# eprom-programmer3.net
KiCad netlist of a schematic drawn in EAGLE
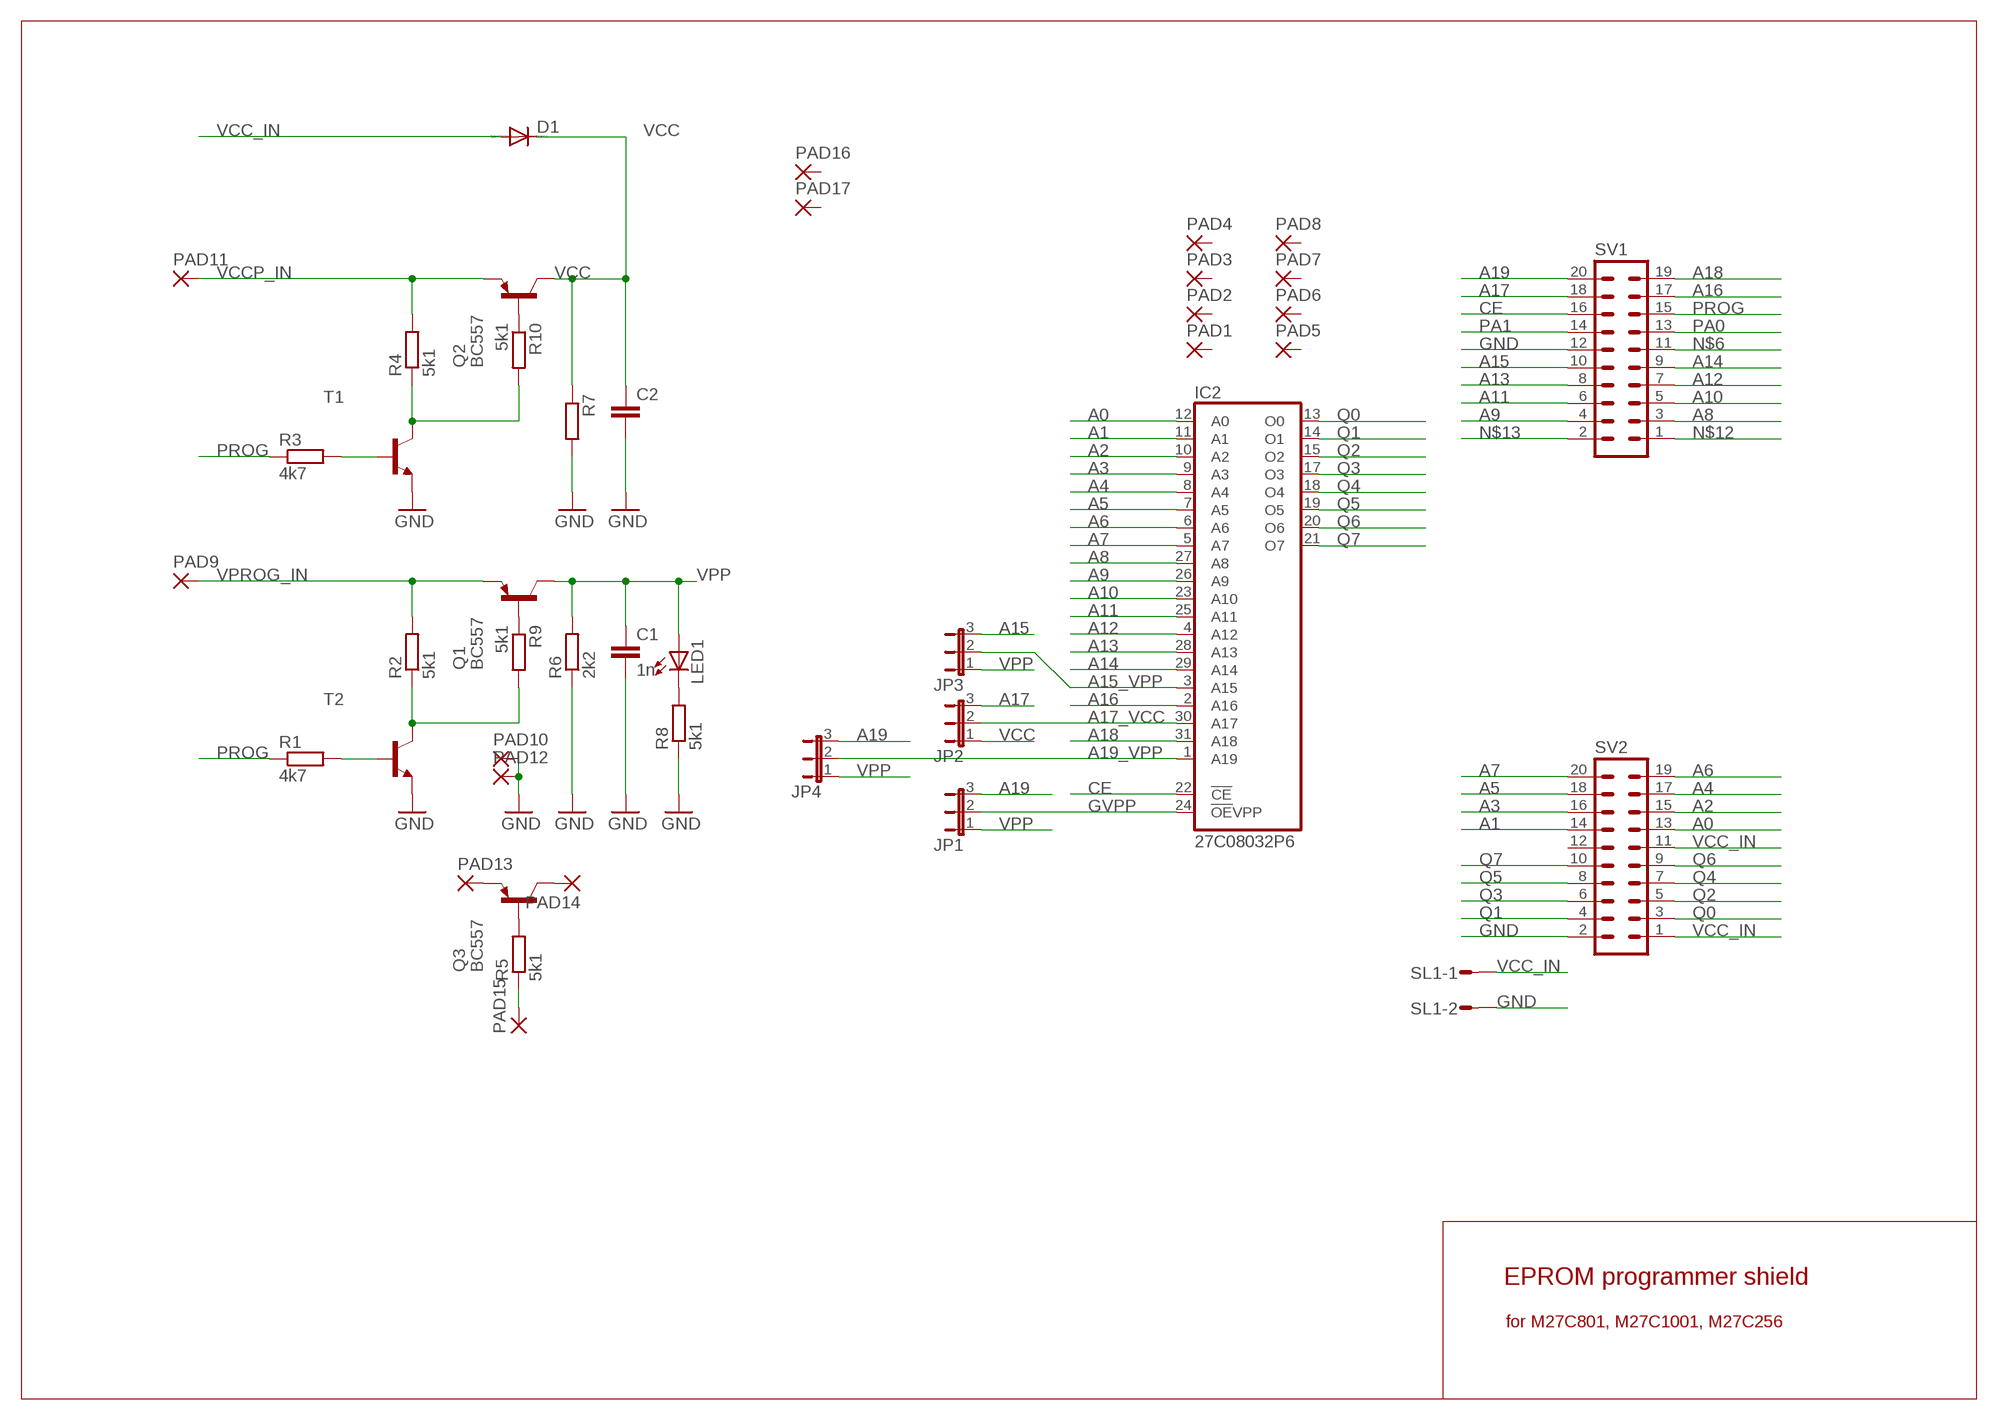
[diagram p0: schematic, sheet 1]

(export (version "E")
  (design (tool "Eeschema 10.0.6"))
  (components
    (comp (ref "C1")
      (value "1n")
      (footprint "eagle-import:C025-024X044")
      (libsource (lib "eagle-import") (part "C-EU025-024X044"))
    )
    (comp (ref "C2")
      (value "C-EUC0805")
      (footprint "eagle-import:C0805")
      (libsource (lib "eagle-import") (part "C-EUC0805"))
    )
    (comp (ref "D1")
      (value "DIODE-MINIMELF")
      (footprint "eagle-import:MINIMELF")
      (libsource (lib "eagle-import") (part "DIODE-MINIMELF"))
    )
    (comp (ref "IC2")
      (value "27C08032P6")
      (footprint "eagle-import:DIL32")
      (fields (field (name "MPN") "AT27C080-90PU"))
      (libsource (lib "eagle-import") (part "27C08032P6"))
    )
    (comp (ref "JP1")
      (value "JP2E")
      (footprint "eagle-import:JP2")
      (libsource (lib "eagle-import") (part "JP2E"))
    )
    (comp (ref "JP2")
      (value "JP2E")
      (footprint "eagle-import:JP2")
      (libsource (lib "eagle-import") (part "JP2E"))
    )
    (comp (ref "JP3")
      (value "JP2E")
      (footprint "eagle-import:JP2")
      (libsource (lib "eagle-import") (part "JP2E"))
    )
    (comp (ref "JP4")
      (value "JP2E")
      (footprint "eagle-import:JP2")
      (libsource (lib "eagle-import") (part "JP2E"))
    )
    (comp (ref "LED1")
      (value "LED3MM")
      (footprint "eagle-import:LED3MM")
      (libsource (lib "eagle-import") (part "LED3MM"))
    )
    (comp (ref "PAD1")
      (value "1,6/0,8")
      (footprint "eagle-import:1,6_0,8")
      (libsource (lib "eagle-import") (part "1,6/0,8"))
    )
    (comp (ref "PAD2")
      (value "1,6/0,8")
      (footprint "eagle-import:1,6_0,8")
      (libsource (lib "eagle-import") (part "1,6/0,8"))
    )
    (comp (ref "PAD3")
      (value "1,6/0,8")
      (footprint "eagle-import:1,6_0,8")
      (libsource (lib "eagle-import") (part "1,6/0,8"))
    )
    (comp (ref "PAD4")
      (value "1,6/0,8")
      (footprint "eagle-import:1,6_0,8")
      (libsource (lib "eagle-import") (part "1,6/0,8"))
    )
    (comp (ref "PAD5")
      (value "1,6/0,8")
      (footprint "eagle-import:1,6_0,8")
      (libsource (lib "eagle-import") (part "1,6/0,8"))
    )
    (comp (ref "PAD6")
      (value "1,6/0,8")
      (footprint "eagle-import:1,6_0,8")
      (libsource (lib "eagle-import") (part "1,6/0,8"))
    )
    (comp (ref "PAD7")
      (value "1,6/0,8")
      (footprint "eagle-import:1,6_0,8")
      (libsource (lib "eagle-import") (part "1,6/0,8"))
    )
    (comp (ref "PAD8")
      (value "1,6/0,8")
      (footprint "eagle-import:1,6_0,8")
      (libsource (lib "eagle-import") (part "1,6/0,8"))
    )
    (comp (ref "PAD9")
      (value "1,6/0,8")
      (footprint "eagle-import:1,6_0,8")
      (libsource (lib "eagle-import") (part "1,6/0,8"))
    )
    (comp (ref "PAD10")
      (value "1,6/0,8")
      (footprint "eagle-import:1,6_0,8")
      (libsource (lib "eagle-import") (part "1,6/0,8"))
    )
    (comp (ref "PAD11")
      (value "1,6/0,8")
      (footprint "eagle-import:1,6_0,8")
      (libsource (lib "eagle-import") (part "1,6/0,8"))
    )
    (comp (ref "PAD12")
      (value "1,6/0,8")
      (footprint "eagle-import:1,6_0,8")
      (libsource (lib "eagle-import") (part "1,6/0,8"))
    )
    (comp (ref "PAD13")
      (value "1,6/0,8")
      (footprint "eagle-import:1,6_0,8")
      (libsource (lib "eagle-import") (part "1,6/0,8"))
    )
    (comp (ref "PAD14")
      (value "1,6/0,8")
      (footprint "eagle-import:1,6_0,8")
      (libsource (lib "eagle-import") (part "1,6/0,8"))
    )
    (comp (ref "PAD15")
      (value "1,6/0,8")
      (footprint "eagle-import:1,6_0,8")
      (libsource (lib "eagle-import") (part "1,6/0,8"))
    )
    (comp (ref "PAD16")
      (value "1,6/0,8")
      (footprint "eagle-import:1,6_0,8")
      (libsource (lib "eagle-import") (part "1,6/0,8"))
    )
    (comp (ref "PAD17")
      (value "1,6/0,8")
      (footprint "eagle-import:1,6_0,8")
      (libsource (lib "eagle-import") (part "1,6/0,8"))
    )
    (comp (ref "Q1")
      (value "BC557")
      (footprint "eagle-import:TO92-EBC")
      (libsource (lib "eagle-import") (part "BC557"))
    )
    (comp (ref "Q2")
      (value "BC557")
      (footprint "eagle-import:TO92-EBC")
      (libsource (lib "eagle-import") (part "BC557"))
    )
    (comp (ref "Q3")
      (value "BC557")
      (footprint "eagle-import:TO92-EBC")
      (libsource (lib "eagle-import") (part "BC557"))
    )
    (comp (ref "R1")
      (value "4k7")
      (footprint "eagle-import:0207_2V")
      (libsource (lib "eagle-import") (part "R-EU_0207/2V"))
    )
    (comp (ref "R2")
      (value "5k1")
      (footprint "eagle-import:0207_2V")
      (libsource (lib "eagle-import") (part "R-EU_0207/2V"))
    )
    (comp (ref "R3")
      (value "4k7")
      (footprint "eagle-import:0207_2V")
      (libsource (lib "eagle-import") (part "R-EU_0207/2V"))
    )
    (comp (ref "R4")
      (value "5k1")
      (footprint "eagle-import:0207_2V")
      (libsource (lib "eagle-import") (part "R-EU_0207/2V"))
    )
    (comp (ref "R5")
      (value "5k1")
      (footprint "eagle-import:0207_2V")
      (libsource (lib "eagle-import") (part "R-EU_0207/2V"))
    )
    (comp (ref "R6")
      (value "2k2")
      (footprint "eagle-import:0207_2V")
      (libsource (lib "eagle-import") (part "R-EU_0207/2V"))
    )
    (comp (ref "R7")
      (value "R-EU_M0805")
      (footprint "eagle-import:M0805")
      (libsource (lib "eagle-import") (part "R-EU_M0805"))
    )
    (comp (ref "R8")
      (value "5k1")
      (footprint "eagle-import:0207_2V")
      (libsource (lib "eagle-import") (part "R-EU_0207/2V"))
    )
    (comp (ref "R9")
      (value "5k1")
      (footprint "eagle-import:M0805")
      (libsource (lib "eagle-import") (part "R-EU_M0805"))
    )
    (comp (ref "R10")
      (value "5k1")
      (footprint "eagle-import:M0805")
      (libsource (lib "eagle-import") (part "R-EU_M0805"))
    )
    (comp (ref "SL1")
      (value "MA02S")
      (footprint "eagle-import:02PA")
      (libsource (lib "eagle-import") (part "MA02S"))
    )
    (comp (ref "SV1")
      (value "MA10-2")
      (footprint "eagle-import:MA10-2")
      (libsource (lib "eagle-import") (part "MA10-2"))
    )
    (comp (ref "SV2")
      (value "MA10-2")
      (footprint "eagle-import:MA10-2")
      (libsource (lib "eagle-import") (part "MA10-2"))
    )
    (comp (ref "T1")
      (value "BC547-NPN-TO92-CBE")
      (footprint "eagle-import:TO92-CBE")
      (libsource (lib "eagle-import") (part "-NPN-TO92-CBEBC547"))
    )
    (comp (ref "T2")
      (value "BC547-NPN-TO92-CBE")
      (footprint "eagle-import:TO92-CBE")
      (libsource (lib "eagle-import") (part "-NPN-TO92-CBEBC547"))
    )
  )
  (nets
    (net (code "1") (name "/A0") (class "Default")
      (node (ref "IC2") (pin "12") (pinfunction "A0_12") (pintype "input"))
      (node (ref "SV2") (pin "13") (pinfunction "13_13") (pintype "passive"))
    )
    (net (code "2") (name "/A1") (class "Default")
      (node (ref "IC2") (pin "11") (pinfunction "A1_11") (pintype "input"))
      (node (ref "SV2") (pin "14") (pinfunction "14_14") (pintype "passive"))
    )
    (net (code "3") (name "/A2") (class "Default")
      (node (ref "IC2") (pin "10") (pinfunction "A2_10") (pintype "input"))
      (node (ref "SV2") (pin "15") (pinfunction "15_15") (pintype "passive"))
    )
    (net (code "4") (name "/A3") (class "Default")
      (node (ref "IC2") (pin "9") (pinfunction "A3_9") (pintype "input"))
      (node (ref "SV2") (pin "16") (pinfunction "16_16") (pintype "passive"))
    )
    (net (code "5") (name "/A4") (class "Default")
      (node (ref "IC2") (pin "8") (pinfunction "A4_8") (pintype "input"))
      (node (ref "SV2") (pin "17") (pinfunction "17_17") (pintype "passive"))
    )
    (net (code "6") (name "/A5") (class "Default")
      (node (ref "IC2") (pin "7") (pinfunction "A5_7") (pintype "input"))
      (node (ref "SV2") (pin "18") (pinfunction "18_18") (pintype "passive"))
    )
    (net (code "7") (name "/A6") (class "Default")
      (node (ref "IC2") (pin "6") (pinfunction "A6_6") (pintype "input"))
      (node (ref "SV2") (pin "19") (pinfunction "19_19") (pintype "passive"))
    )
    (net (code "8") (name "/A7") (class "Default")
      (node (ref "IC2") (pin "5") (pinfunction "A7_5") (pintype "input"))
      (node (ref "SV2") (pin "20") (pinfunction "20_20") (pintype "passive"))
    )
    (net (code "9") (name "/A8") (class "Default")
      (node (ref "IC2") (pin "27") (pinfunction "A8_27") (pintype "input"))
      (node (ref "SV1") (pin "3") (pinfunction "3_3") (pintype "passive"))
    )
    (net (code "10") (name "/A9") (class "Default")
      (node (ref "IC2") (pin "26") (pinfunction "A9_26") (pintype "input"))
      (node (ref "SV1") (pin "4") (pinfunction "4_4") (pintype "passive"))
    )
    (net (code "11") (name "/A10") (class "Default")
      (node (ref "IC2") (pin "23") (pinfunction "A10_23") (pintype "input"))
      (node (ref "SV1") (pin "5") (pinfunction "5_5") (pintype "passive"))
    )
    (net (code "12") (name "/A11") (class "Default")
      (node (ref "IC2") (pin "25") (pinfunction "A11_25") (pintype "input"))
      (node (ref "SV1") (pin "6") (pinfunction "6_6") (pintype "passive"))
    )
    (net (code "13") (name "/A12") (class "Default")
      (node (ref "IC2") (pin "4") (pinfunction "A12_4") (pintype "input"))
      (node (ref "SV1") (pin "7") (pinfunction "7_7") (pintype "passive"))
    )
    (net (code "14") (name "/A13") (class "Default")
      (node (ref "IC2") (pin "28") (pinfunction "A13_28") (pintype "input"))
      (node (ref "SV1") (pin "8") (pinfunction "8_8") (pintype "passive"))
    )
    (net (code "15") (name "/A14") (class "Default")
      (node (ref "IC2") (pin "29") (pinfunction "A14_29") (pintype "input"))
      (node (ref "SV1") (pin "9") (pinfunction "9_9") (pintype "passive"))
    )
    (net (code "16") (name "/A15") (class "Default")
      (node (ref "JP3") (pin "3") (pinfunction "3_3") (pintype "passive"))
      (node (ref "SV1") (pin "10") (pinfunction "10_10") (pintype "passive"))
    )
    (net (code "17") (name "/A15_VPP") (class "Default")
      (node (ref "IC2") (pin "3") (pinfunction "A15_3") (pintype "input"))
      (node (ref "JP3") (pin "2") (pinfunction "2_2") (pintype "passive"))
    )
    (net (code "18") (name "/A16") (class "Default")
      (node (ref "IC2") (pin "2") (pinfunction "A16_2") (pintype "input"))
      (node (ref "SV1") (pin "17") (pinfunction "17_17") (pintype "passive"))
    )
    (net (code "19") (name "/A17") (class "Default")
      (node (ref "JP2") (pin "3") (pinfunction "3_3") (pintype "passive"))
      (node (ref "SV1") (pin "18") (pinfunction "18_18") (pintype "passive"))
    )
    (net (code "20") (name "/A17_VCC") (class "Default")
      (node (ref "IC2") (pin "30") (pinfunction "A17_30") (pintype "input"))
      (node (ref "JP2") (pin "2") (pinfunction "2_2") (pintype "passive"))
    )
    (net (code "21") (name "/A18") (class "Default")
      (node (ref "IC2") (pin "31") (pinfunction "A18_31") (pintype "input"))
      (node (ref "SV1") (pin "19") (pinfunction "19_19") (pintype "passive"))
    )
    (net (code "22") (name "/A19") (class "Default")
      (node (ref "JP1") (pin "3") (pinfunction "3_3") (pintype "passive"))
      (node (ref "JP4") (pin "3") (pinfunction "3_3") (pintype "passive"))
      (node (ref "SV1") (pin "20") (pinfunction "20_20") (pintype "passive"))
    )
    (net (code "23") (name "/A19_VPP") (class "Default")
      (node (ref "IC2") (pin "1") (pinfunction "A19_1") (pintype "input"))
      (node (ref "JP4") (pin "2") (pinfunction "2_2") (pintype "passive"))
    )
    (net (code "24") (name "/CE") (class "Default")
      (node (ref "IC2") (pin "22") (pinfunction "~{CE}_22") (pintype "input"))
      (node (ref "SV1") (pin "16") (pinfunction "16_16") (pintype "passive"))
    )
    (net (code "25") (name "/GVPP") (class "Default")
      (node (ref "IC2") (pin "24") (pinfunction "~{OE}VPP_24") (pintype "input"))
      (node (ref "JP1") (pin "2") (pinfunction "2_2") (pintype "passive"))
    )
    (net (code "26") (name "/N$6") (class "Default")
      (node (ref "SV1") (pin "11") (pinfunction "11_11") (pintype "passive"))
    )
    (net (code "27") (name "/N$12") (class "Default")
      (node (ref "SV1") (pin "1") (pinfunction "1_1") (pintype "passive"))
    )
    (net (code "28") (name "/N$13") (class "Default")
      (node (ref "SV1") (pin "2") (pinfunction "2_2") (pintype "passive"))
    )
    (net (code "29") (name "/PA0") (class "Default")
      (node (ref "SV1") (pin "13") (pinfunction "13_13") (pintype "passive"))
    )
    (net (code "30") (name "/PA1") (class "Default")
      (node (ref "SV1") (pin "14") (pinfunction "14_14") (pintype "passive"))
    )
    (net (code "31") (name "/PROG") (class "Default")
      (node (ref "R1") (pin "1") (pinfunction "1_1") (pintype "passive"))
      (node (ref "R3") (pin "1") (pinfunction "1_1") (pintype "passive"))
      (node (ref "SV1") (pin "15") (pinfunction "15_15") (pintype "passive"))
    )
    (net (code "32") (name "/Q0") (class "Default")
      (node (ref "IC2") (pin "13") (pinfunction "O0_13") (pintype "tri_state"))
      (node (ref "SV2") (pin "3") (pinfunction "3_3") (pintype "passive"))
    )
    (net (code "33") (name "/Q1") (class "Default")
      (node (ref "IC2") (pin "14") (pinfunction "O1_14") (pintype "tri_state"))
      (node (ref "SV2") (pin "4") (pinfunction "4_4") (pintype "passive"))
    )
    (net (code "34") (name "/Q2") (class "Default")
      (node (ref "IC2") (pin "15") (pinfunction "O2_15") (pintype "tri_state"))
      (node (ref "SV2") (pin "5") (pinfunction "5_5") (pintype "passive"))
    )
    (net (code "35") (name "/Q3") (class "Default")
      (node (ref "IC2") (pin "17") (pinfunction "O3_17") (pintype "tri_state"))
      (node (ref "SV2") (pin "6") (pinfunction "6_6") (pintype "passive"))
    )
    (net (code "36") (name "/Q4") (class "Default")
      (node (ref "IC2") (pin "18") (pinfunction "O4_18") (pintype "tri_state"))
      (node (ref "SV2") (pin "7") (pinfunction "7_7") (pintype "passive"))
    )
    (net (code "37") (name "/Q5") (class "Default")
      (node (ref "IC2") (pin "19") (pinfunction "O5_19") (pintype "tri_state"))
      (node (ref "SV2") (pin "8") (pinfunction "8_8") (pintype "passive"))
    )
    (net (code "38") (name "/Q6") (class "Default")
      (node (ref "IC2") (pin "20") (pinfunction "O6_20") (pintype "tri_state"))
      (node (ref "SV2") (pin "9") (pinfunction "9_9") (pintype "passive"))
    )
    (net (code "39") (name "/Q7") (class "Default")
      (node (ref "IC2") (pin "21") (pinfunction "O7_21") (pintype "tri_state"))
      (node (ref "SV2") (pin "10") (pinfunction "10_10") (pintype "passive"))
    )
    (net (code "40") (name "/VCC") (class "Default")
      (node (ref "C2") (pin "1") (pinfunction "1_1") (pintype "passive"))
      (node (ref "D1") (pin "C") (pinfunction "C_C") (pintype "passive"))
      (node (ref "JP2") (pin "1") (pinfunction "1_1") (pintype "passive"))
      (node (ref "Q2") (pin "C") (pinfunction "C_C") (pintype "passive"))
      (node (ref "R7") (pin "1") (pinfunction "1_1") (pintype "passive"))
    )
    (net (code "41") (name "/VCCP_IN") (class "Default")
      (node (ref "PAD11") (pin "1") (pinfunction "P_1") (pintype "passive"))
      (node (ref "Q2") (pin "E") (pinfunction "E_E") (pintype "passive"))
      (node (ref "R4") (pin "2") (pinfunction "2_2") (pintype "passive"))
    )
    (net (code "42") (name "/VCC_IN") (class "Default")
      (node (ref "D1") (pin "A") (pinfunction "A_A") (pintype "passive"))
      (node (ref "SL1") (pin "1") (pinfunction "S_1") (pintype "passive"))
      (node (ref "SV2") (pin "1") (pinfunction "1_1") (pintype "passive"))
      (node (ref "SV2") (pin "11") (pinfunction "11_11") (pintype "passive"))
    )
    (net (code "43") (name "/VPP") (class "Default")
      (node (ref "C1") (pin "1") (pinfunction "1_1") (pintype "passive"))
      (node (ref "JP1") (pin "1") (pinfunction "1_1") (pintype "passive"))
      (node (ref "JP3") (pin "1") (pinfunction "1_1") (pintype "passive"))
      (node (ref "JP4") (pin "1") (pinfunction "1_1") (pintype "passive"))
      (node (ref "LED1") (pin "A") (pinfunction "A_A") (pintype "passive"))
      (node (ref "Q1") (pin "C") (pinfunction "C_C") (pintype "passive"))
      (node (ref "R6") (pin "2") (pinfunction "2_2") (pintype "passive"))
    )
    (net (code "44") (name "/VPROG_IN") (class "Default")
      (node (ref "PAD9") (pin "1") (pinfunction "P_1") (pintype "passive"))
      (node (ref "Q1") (pin "E") (pinfunction "E_E") (pintype "passive"))
      (node (ref "R2") (pin "2") (pinfunction "2_2") (pintype "passive"))
    )
    (net (code "45") (name "GND") (class "Default")
      (node (ref "C1") (pin "2") (pinfunction "2_2") (pintype "passive"))
      (node (ref "C2") (pin "2") (pinfunction "2_2") (pintype "passive"))
      (node (ref "PAD10") (pin "1") (pinfunction "P_1") (pintype "passive"))
      (node (ref "PAD12") (pin "1") (pinfunction "P_1") (pintype "passive"))
      (node (ref "R6") (pin "1") (pinfunction "1_1") (pintype "passive"))
      (node (ref "R7") (pin "2") (pinfunction "2_2") (pintype "passive"))
      (node (ref "R8") (pin "1") (pinfunction "1_1") (pintype "passive"))
      (node (ref "SL1") (pin "2") (pinfunction "S_2") (pintype "passive"))
      (node (ref "SV1") (pin "12") (pinfunction "12_12") (pintype "passive"))
      (node (ref "SV2") (pin "2") (pinfunction "2_2") (pintype "passive"))
      (node (ref "T1") (pin "E") (pinfunction "E_E") (pintype "passive"))
      (node (ref "T2") (pin "E") (pinfunction "E_E") (pintype "passive"))
    )
    (net (code "46") (name "Net-(LED1-C)") (class "Default")
      (node (ref "LED1") (pin "K") (pinfunction "C_K") (pintype "passive"))
      (node (ref "R8") (pin "2") (pinfunction "2_2") (pintype "passive"))
    )
    (net (code "47") (name "Net-(PAD13-P)") (class "Default")
      (node (ref "PAD13") (pin "1") (pinfunction "P_1") (pintype "passive"))
      (node (ref "Q3") (pin "E") (pinfunction "E_E") (pintype "passive"))
    )
    (net (code "48") (name "Net-(PAD14-P)") (class "Default")
      (node (ref "PAD14") (pin "1") (pinfunction "P_1") (pintype "passive"))
      (node (ref "Q3") (pin "C") (pinfunction "C_C") (pintype "passive"))
    )
    (net (code "49") (name "Net-(PAD15-P)") (class "Default")
      (node (ref "PAD15") (pin "1") (pinfunction "P_1") (pintype "passive"))
      (node (ref "R5") (pin "1") (pinfunction "1_1") (pintype "passive"))
    )
    (net (code "50") (name "Net-(Q1-PadB)") (class "Default")
      (node (ref "Q1") (pin "B") (pinfunction "B_B") (pintype "passive"))
      (node (ref "R9") (pin "1") (pinfunction "1_1") (pintype "passive"))
    )
    (net (code "51") (name "Net-(Q2-PadB)") (class "Default")
      (node (ref "Q2") (pin "B") (pinfunction "B_B") (pintype "passive"))
      (node (ref "R10") (pin "1") (pinfunction "1_1") (pintype "passive"))
    )
    (net (code "52") (name "Net-(Q3-PadB)") (class "Default")
      (node (ref "Q3") (pin "B") (pinfunction "B_B") (pintype "passive"))
      (node (ref "R5") (pin "2") (pinfunction "2_2") (pintype "passive"))
    )
    (net (code "53") (name "Net-(R1-Pad2)") (class "Default")
      (node (ref "R1") (pin "2") (pinfunction "2_2") (pintype "passive"))
      (node (ref "T2") (pin "B") (pinfunction "B_B") (pintype "passive"))
    )
    (net (code "54") (name "Net-(R2-Pad1)") (class "Default")
      (node (ref "R2") (pin "1") (pinfunction "1_1") (pintype "passive"))
      (node (ref "R9") (pin "2") (pinfunction "2_2") (pintype "passive"))
      (node (ref "T2") (pin "C") (pinfunction "C_C") (pintype "passive"))
    )
    (net (code "55") (name "Net-(R3-Pad2)") (class "Default")
      (node (ref "R3") (pin "2") (pinfunction "2_2") (pintype "passive"))
      (node (ref "T1") (pin "B") (pinfunction "B_B") (pintype "passive"))
    )
    (net (code "56") (name "Net-(R10-Pad2)") (class "Default")
      (node (ref "R10") (pin "2") (pinfunction "2_2") (pintype "passive"))
      (node (ref "R4") (pin "1") (pinfunction "1_1") (pintype "passive"))
      (node (ref "T1") (pin "C") (pinfunction "C_C") (pintype "passive"))
    )
    (net (code "57") (name "unconnected-(PAD1-P-Pad1)") (class "Default")
      (node (ref "PAD1") (pin "1") (pinfunction "P_1") (pintype "passive"))
    )
    (net (code "58") (name "unconnected-(PAD2-P-Pad1)") (class "Default")
      (node (ref "PAD2") (pin "1") (pinfunction "P_1") (pintype "passive"))
    )
    (net (code "59") (name "unconnected-(PAD3-P-Pad1)") (class "Default")
      (node (ref "PAD3") (pin "1") (pinfunction "P_1") (pintype "passive"))
    )
    (net (code "60") (name "unconnected-(PAD4-P-Pad1)") (class "Default")
      (node (ref "PAD4") (pin "1") (pinfunction "P_1") (pintype "passive"))
    )
    (net (code "61") (name "unconnected-(PAD5-P-Pad1)") (class "Default")
      (node (ref "PAD5") (pin "1") (pinfunction "P_1") (pintype "passive"))
    )
    (net (code "62") (name "unconnected-(PAD6-P-Pad1)") (class "Default")
      (node (ref "PAD6") (pin "1") (pinfunction "P_1") (pintype "passive"))
    )
    (net (code "63") (name "unconnected-(PAD7-P-Pad1)") (class "Default")
      (node (ref "PAD7") (pin "1") (pinfunction "P_1") (pintype "passive"))
    )
    (net (code "64") (name "unconnected-(PAD8-P-Pad1)") (class "Default")
      (node (ref "PAD8") (pin "1") (pinfunction "P_1") (pintype "passive"))
    )
    (net (code "65") (name "unconnected-(PAD16-P-Pad1)") (class "Default")
      (node (ref "PAD16") (pin "1") (pinfunction "P_1") (pintype "passive"))
    )
    (net (code "66") (name "unconnected-(PAD17-P-Pad1)") (class "Default")
      (node (ref "PAD17") (pin "1") (pinfunction "P_1") (pintype "passive"))
    )
    (net (code "67") (name "unconnected-(SV2-Pad12)") (class "Default")
      (node (ref "SV2") (pin "12") (pinfunction "12_12") (pintype "passive"))
    )
  )
)
